# EasyBMS.net
KiCad netlist of a schematic drawn in EAGLE
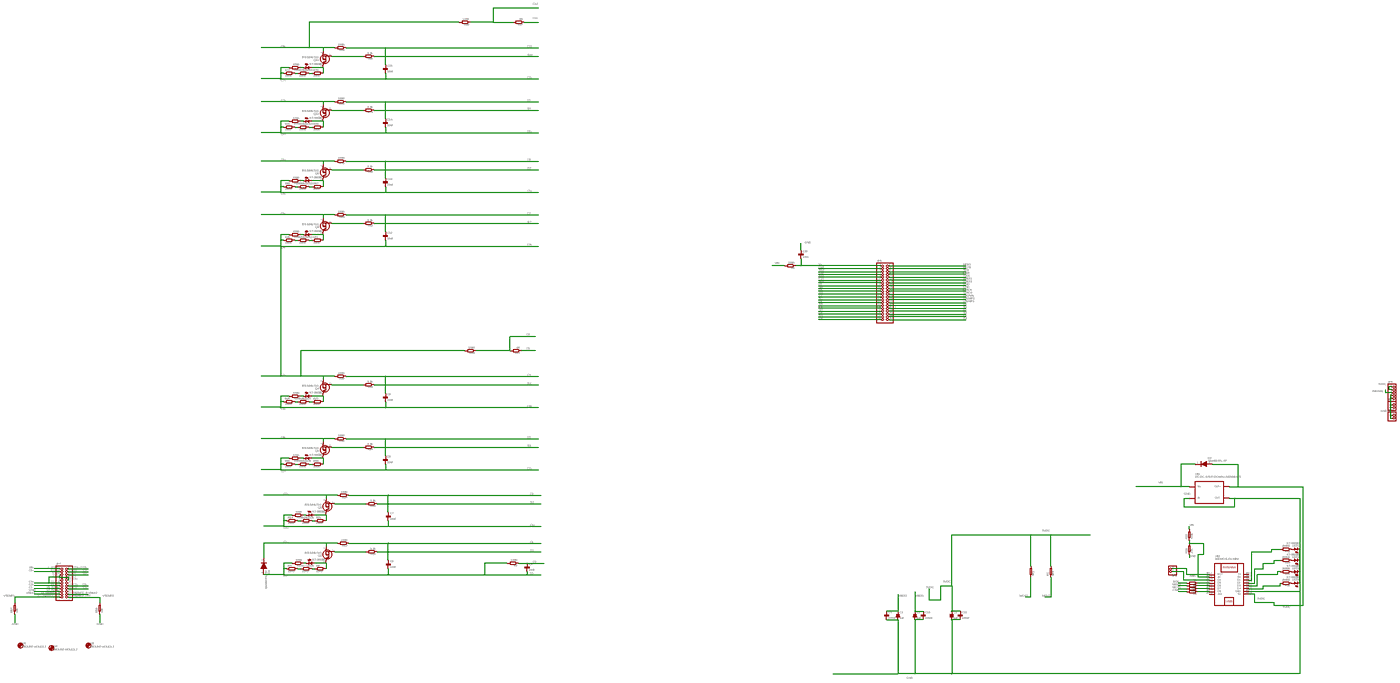
[diagram p0: schematic, sheet 1, overview]
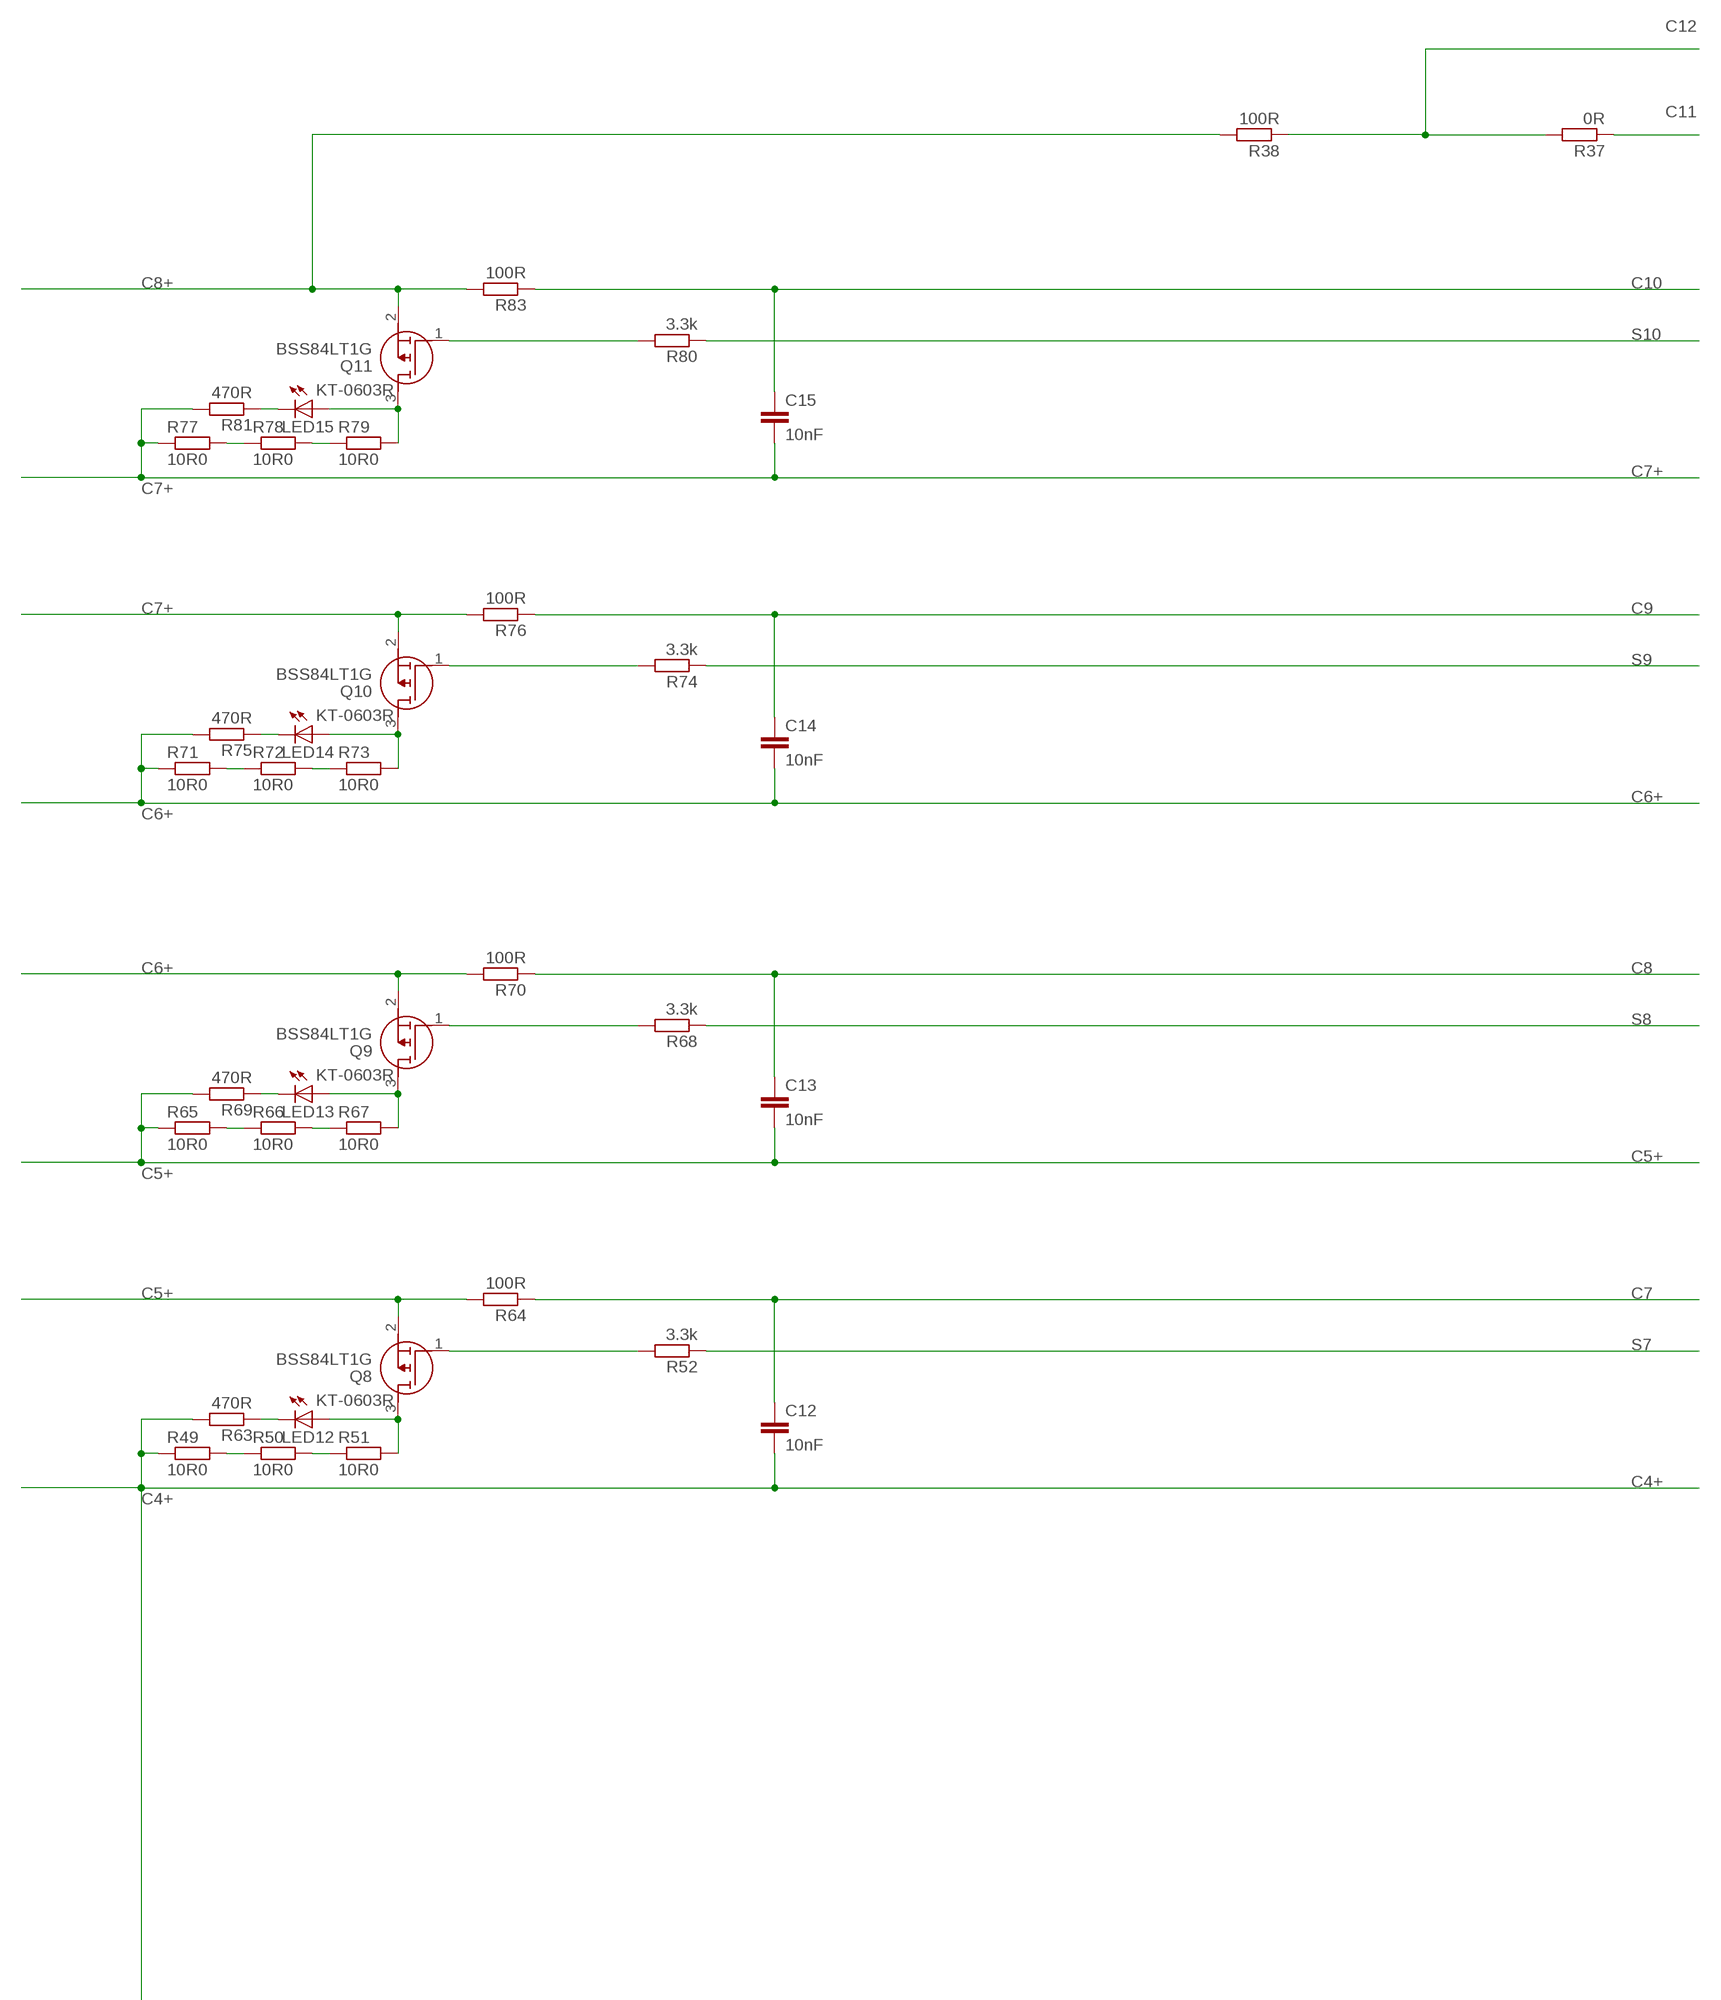
[diagram p1: schematic, sheet 1, part 1 of 4]
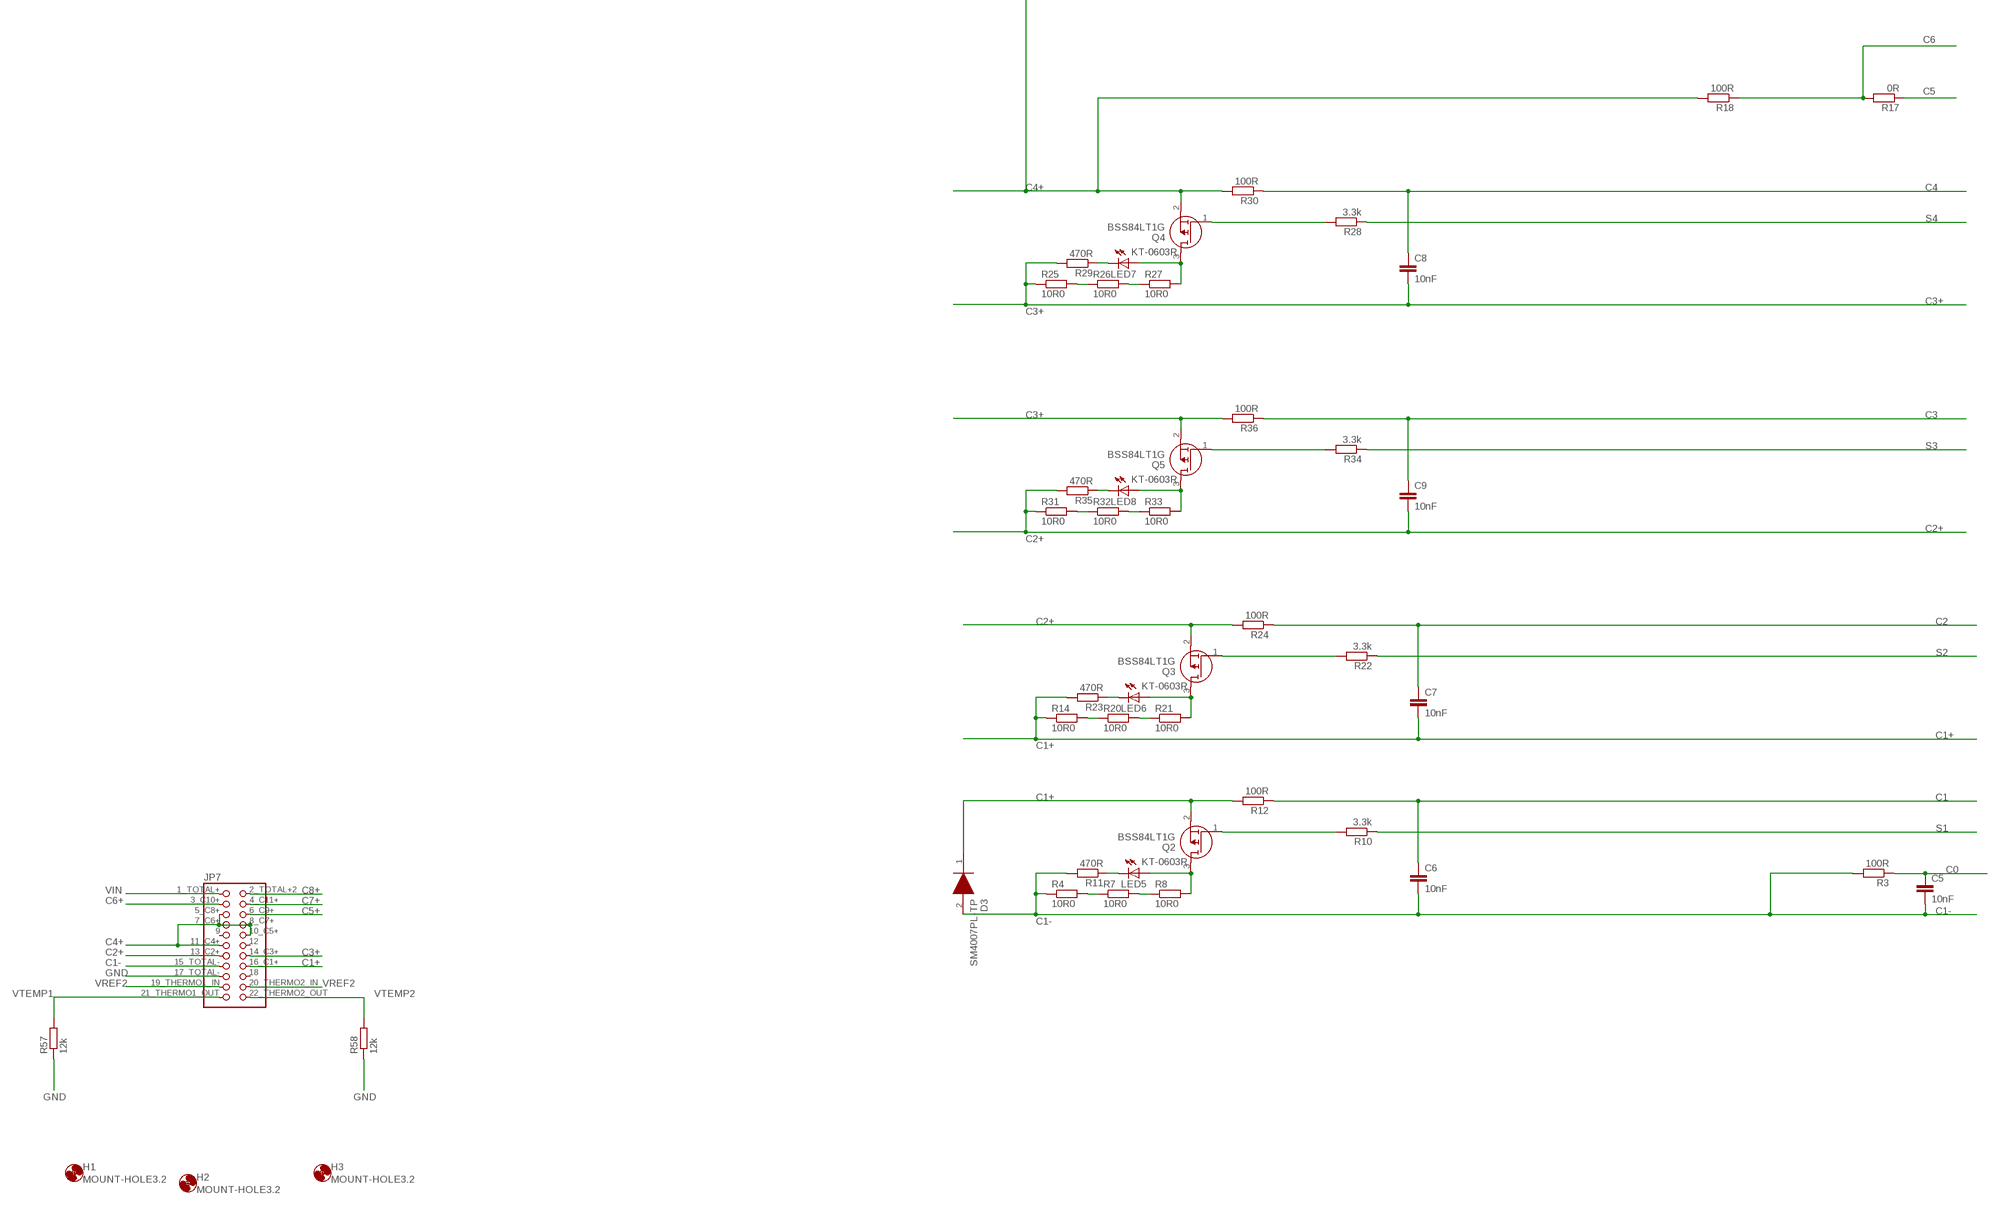
[diagram p2: schematic, sheet 1, part 2 of 4]
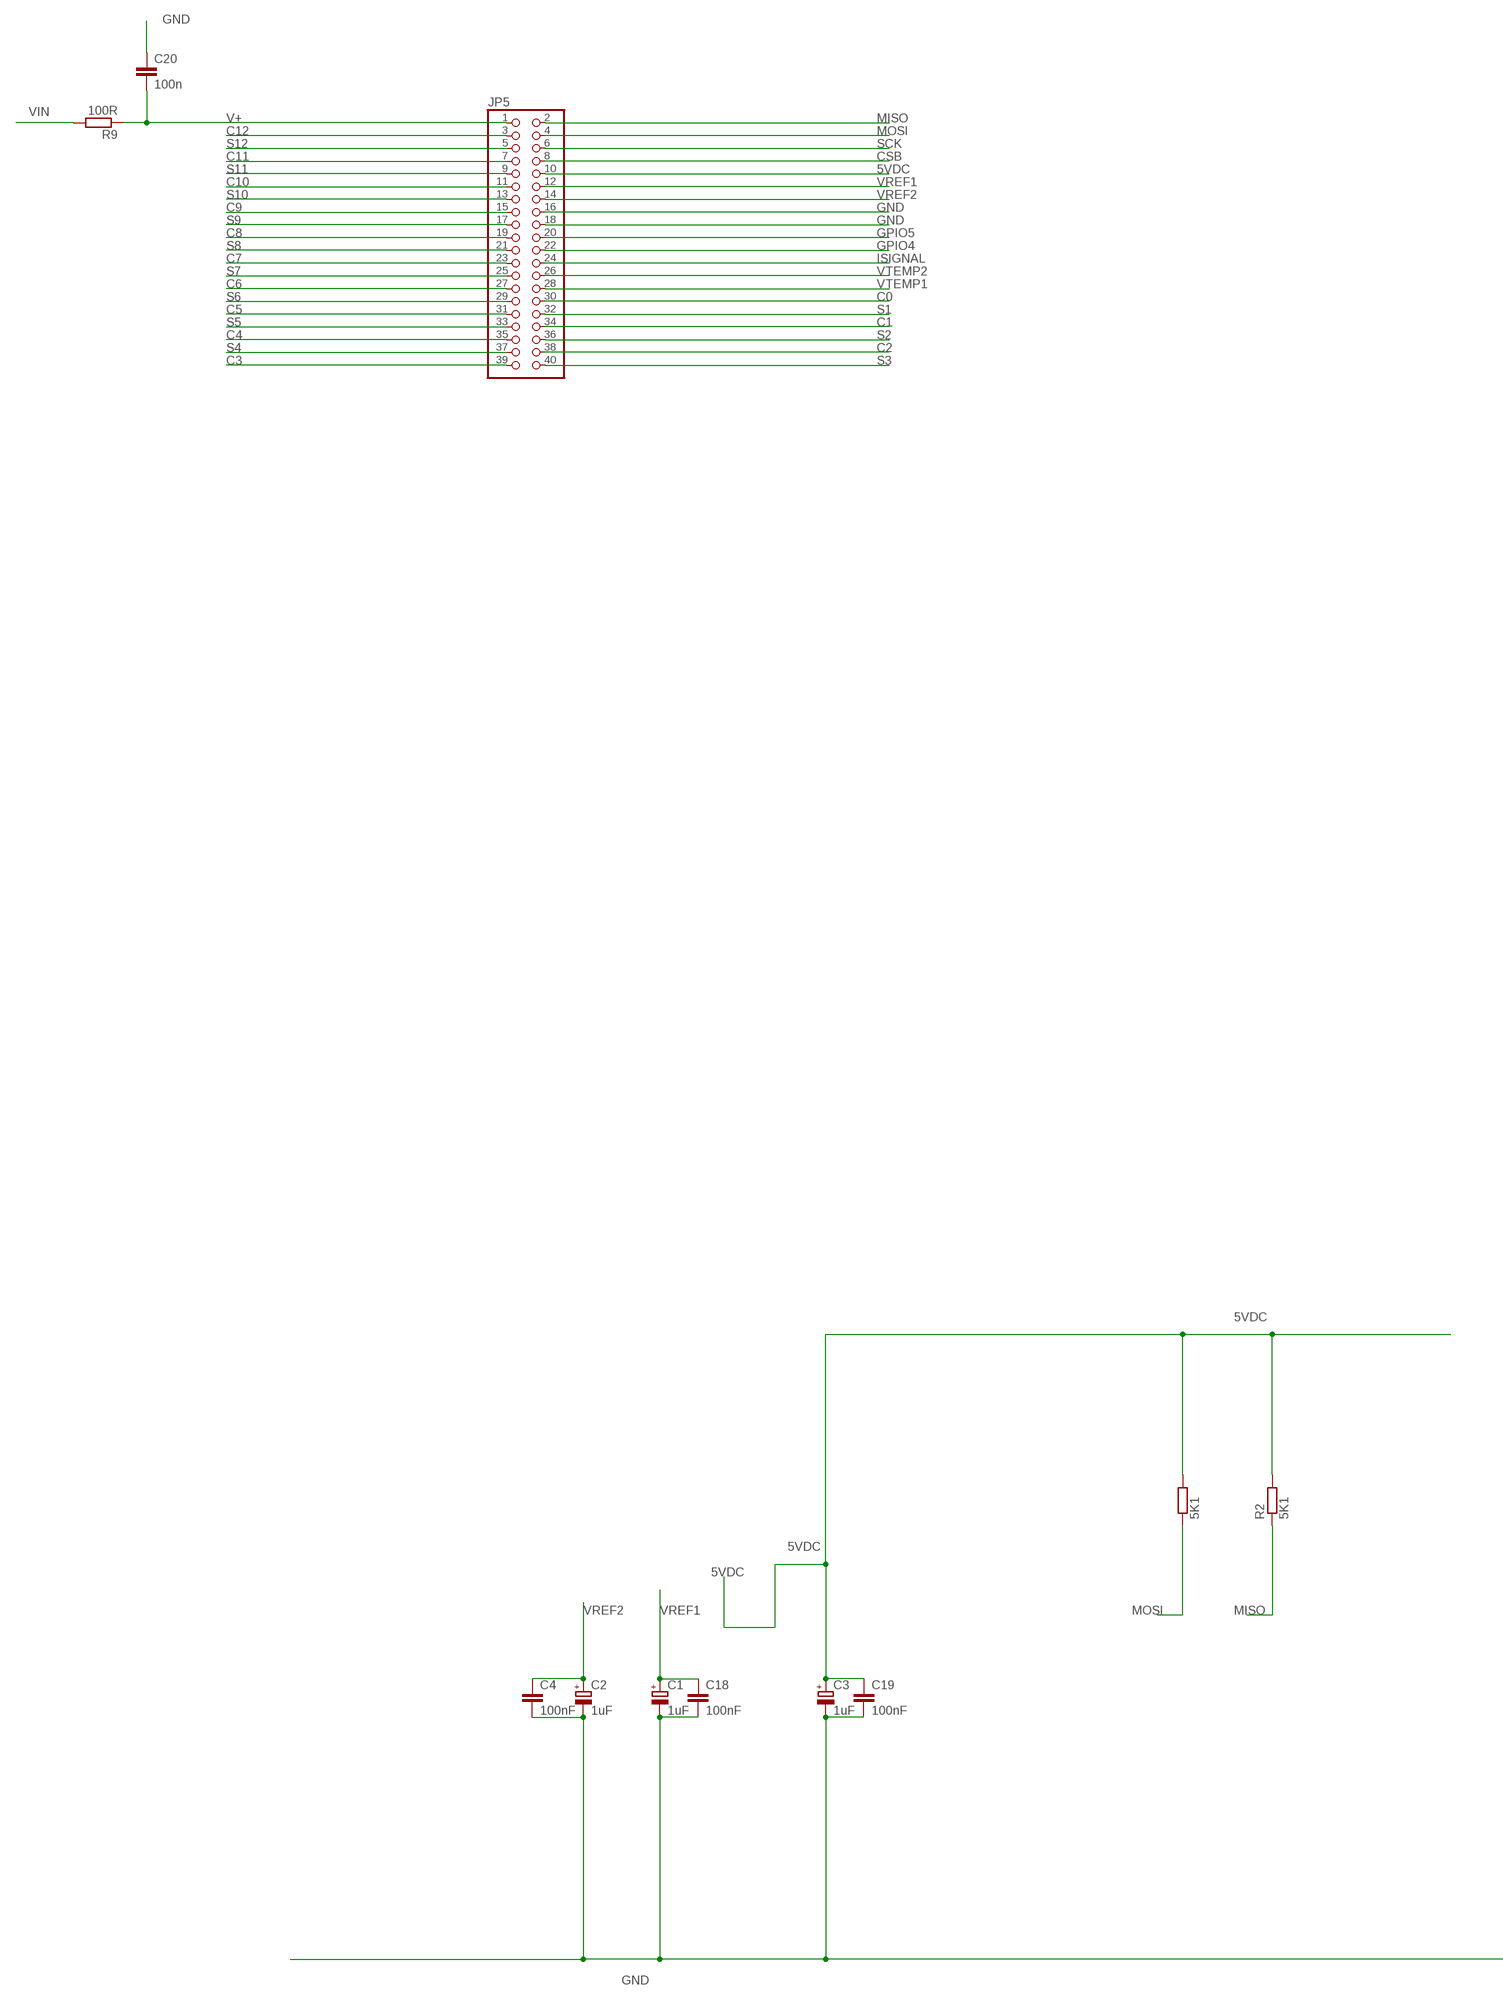
[diagram p3: schematic, sheet 1, part 3 of 4]
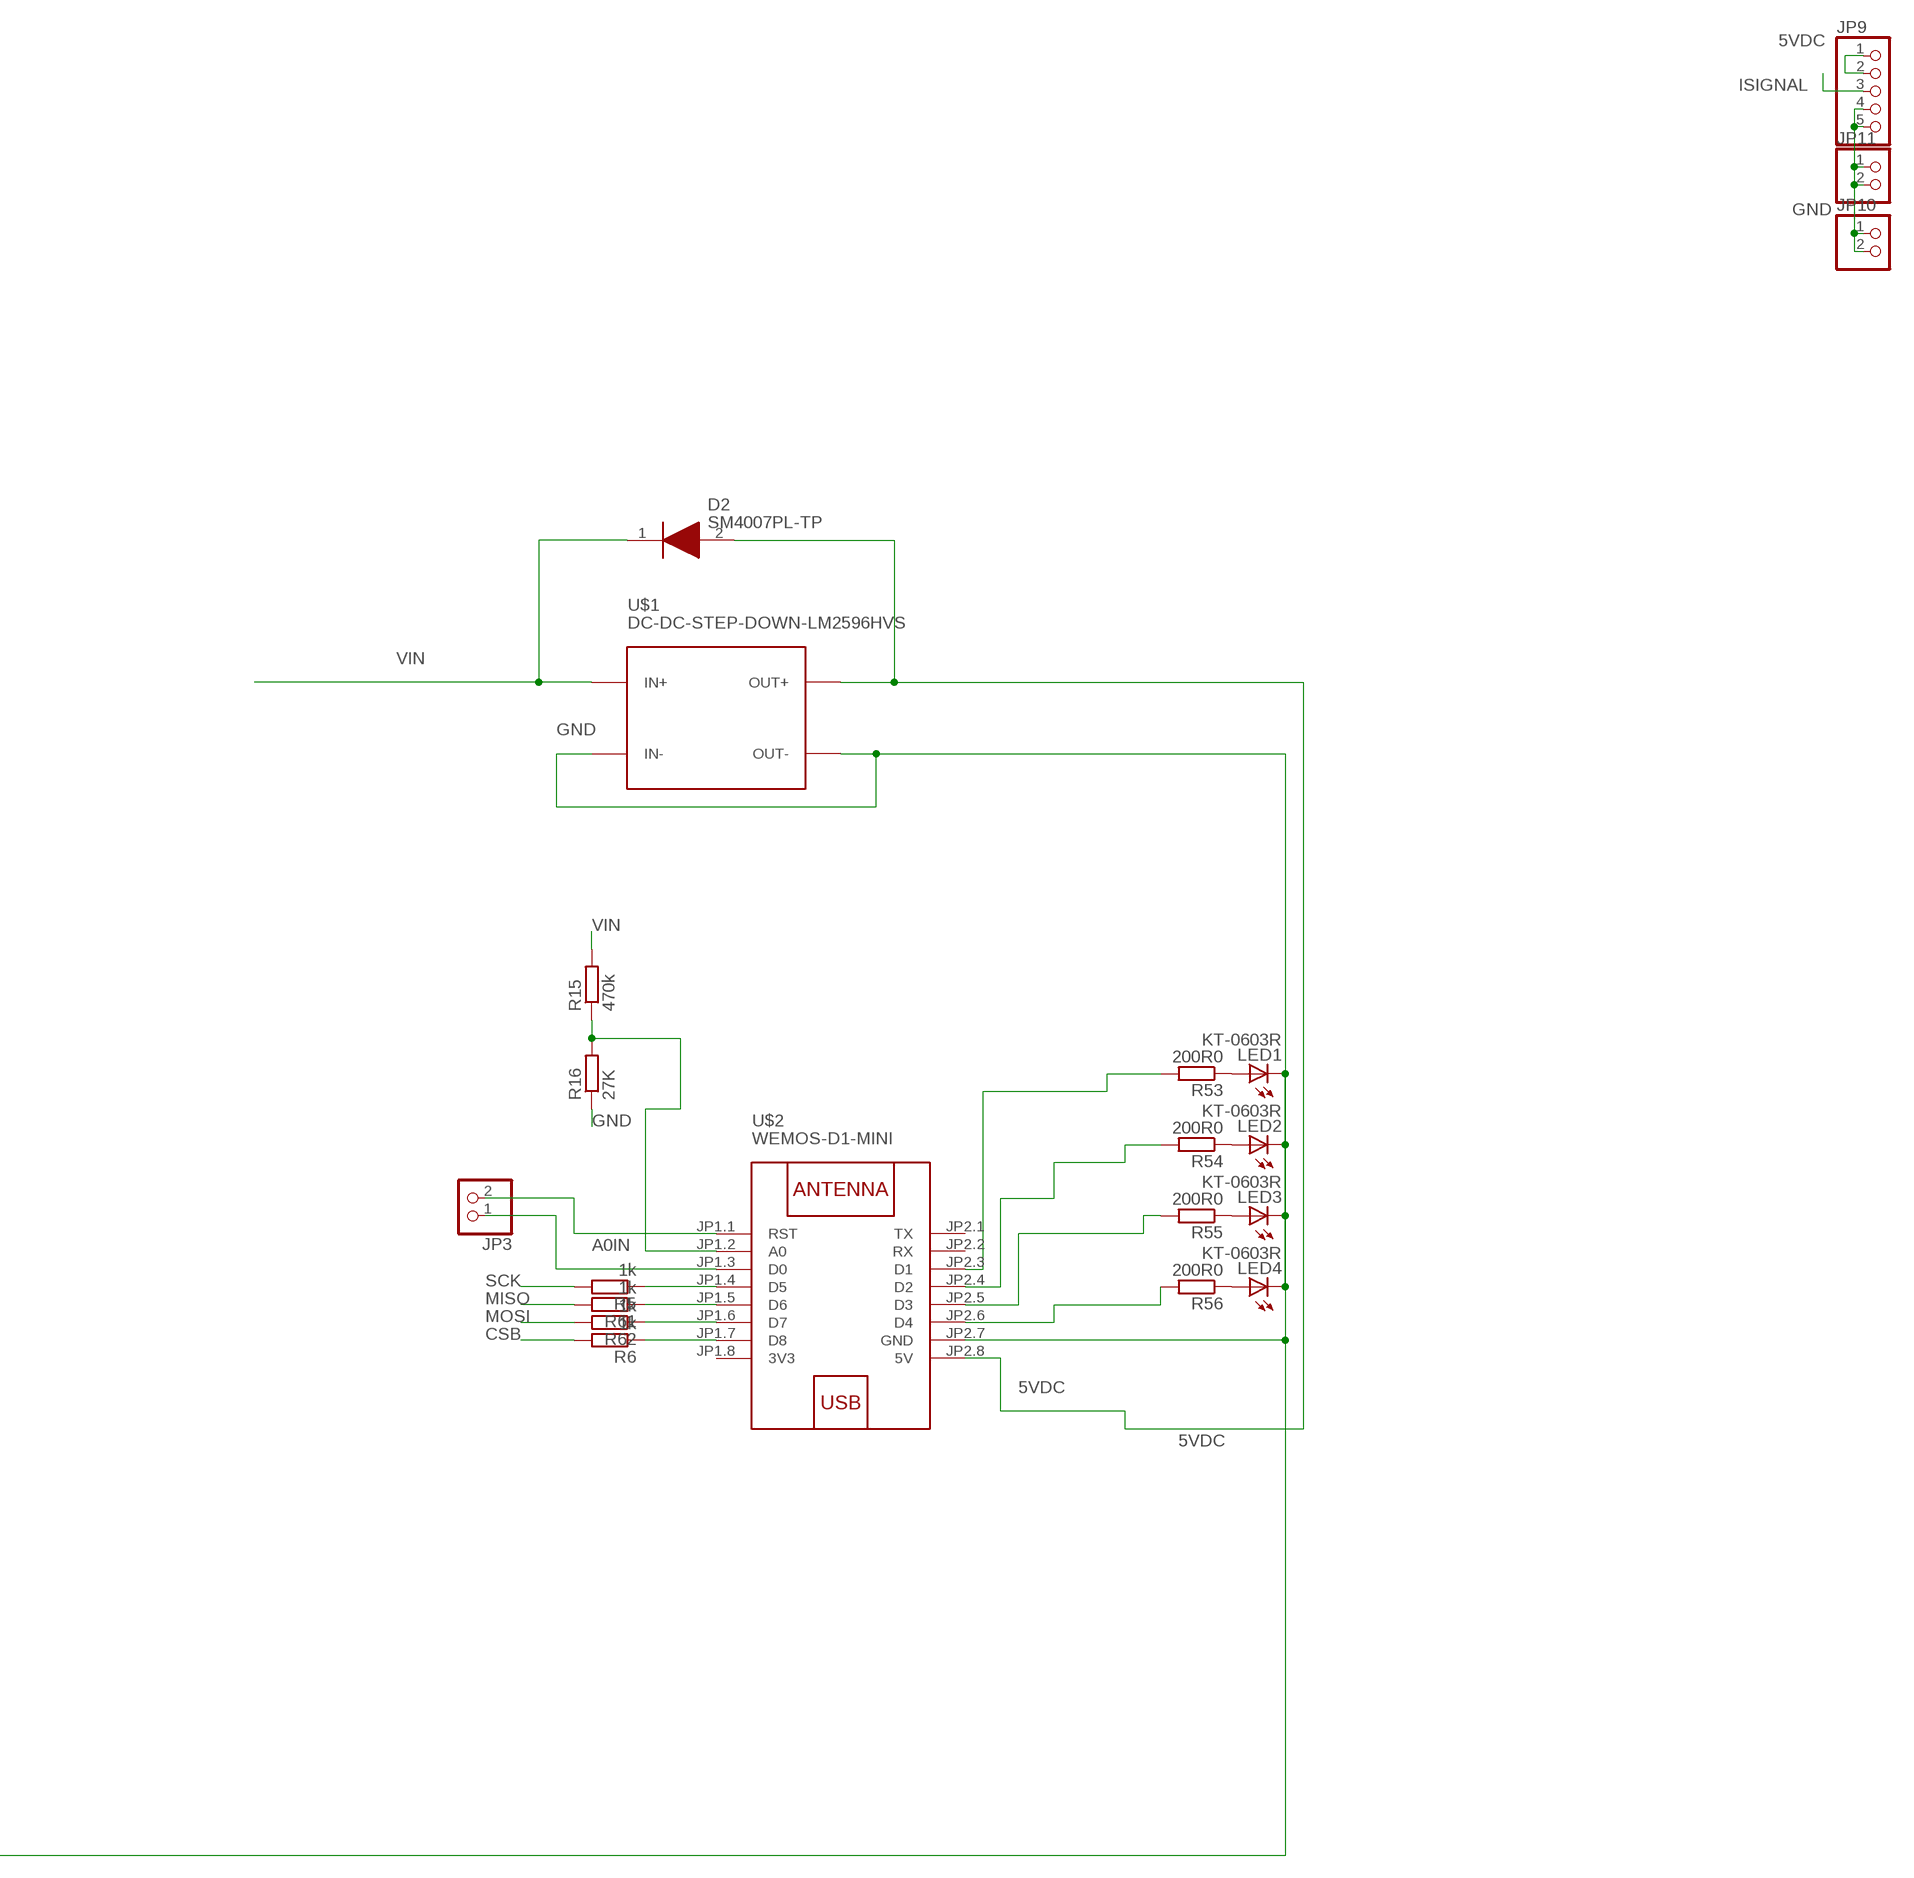
[diagram p4: schematic, sheet 1, part 4 of 4]

(export (version "E")
  (design (tool "Eeschema 10.0.6"))
  (components
    (comp (ref "C1")
      (value "1uF")
      (footprint "eagle-import:E2,5-6")
      (libsource (lib "eagle-import") (part "CPOL-EUE2.5-6"))
    )
    (comp (ref "C2")
      (value "1uF")
      (footprint "eagle-import:E2,5-6")
      (libsource (lib "eagle-import") (part "CPOL-EUE2.5-6"))
    )
    (comp (ref "C3")
      (value "1uF")
      (footprint "eagle-import:E2,5-6")
      (libsource (lib "eagle-import") (part "CPOL-EUE2.5-6"))
    )
    (comp (ref "C4")
      (value "100nF")
      (footprint "eagle-import:C1206")
      (libsource (lib "eagle-import") (part "C-EUC1206"))
    )
    (comp (ref "C5")
      (value "10nF")
      (footprint "eagle-import:C0402")
      (libsource (lib "eagle-import") (part "C-EUC0402"))
    )
    (comp (ref "C6")
      (value "10nF")
      (footprint "eagle-import:C0402")
      (libsource (lib "eagle-import") (part "C-EUC0402"))
    )
    (comp (ref "C7")
      (value "10nF")
      (footprint "eagle-import:C0402")
      (libsource (lib "eagle-import") (part "C-EUC0402"))
    )
    (comp (ref "C8")
      (value "10nF")
      (footprint "eagle-import:C0402")
      (libsource (lib "eagle-import") (part "C-EUC0402"))
    )
    (comp (ref "C9")
      (value "10nF")
      (footprint "eagle-import:C0402")
      (libsource (lib "eagle-import") (part "C-EUC0402"))
    )
    (comp (ref "C12")
      (value "10nF")
      (footprint "eagle-import:C0402")
      (libsource (lib "eagle-import") (part "C-EUC0402"))
    )
    (comp (ref "C13")
      (value "10nF")
      (footprint "eagle-import:C0402")
      (libsource (lib "eagle-import") (part "C-EUC0402"))
    )
    (comp (ref "C14")
      (value "10nF")
      (footprint "eagle-import:C0402")
      (libsource (lib "eagle-import") (part "C-EUC0402"))
    )
    (comp (ref "C15")
      (value "10nF")
      (footprint "eagle-import:C0402")
      (libsource (lib "eagle-import") (part "C-EUC0402"))
    )
    (comp (ref "C18")
      (value "100nF")
      (footprint "eagle-import:C1206")
      (libsource (lib "eagle-import") (part "C-EUC1206"))
    )
    (comp (ref "C19")
      (value "100nF")
      (footprint "eagle-import:C1206")
      (libsource (lib "eagle-import") (part "C-EUC1206"))
    )
    (comp (ref "C20")
      (value "100n")
      (footprint "eagle-import:C0402")
      (libsource (lib "eagle-import") (part "C-EUC0402"))
    )
    (comp (ref "D2")
      (value "SM4007PL-TP")
      (footprint "eagle-import:SODFL3616X135N")
      (fields (field (name "MOUSER_PART_NUMBER") "833-SM4007PL-TP"))
      (libsource (lib "eagle-import") (part "SM4007PL-TP"))
    )
    (comp (ref "D3")
      (value "SM4007PL-TP")
      (footprint "eagle-import:SODFL3616X135N")
      (fields (field (name "MOUSER_PART_NUMBER") "833-SM4007PL-TP"))
      (libsource (lib "eagle-import") (part "SM4007PL-TP"))
    )
    (comp (ref "H1")
      (value "MOUNT-HOLE3.2")
      (footprint "eagle-import:3,2")
      (libsource (lib "eagle-import") (part "MOUNT-HOLE3.2"))
    )
    (comp (ref "H2")
      (value "MOUNT-HOLE3.2")
      (footprint "eagle-import:3,2")
      (libsource (lib "eagle-import") (part "MOUNT-HOLE3.2"))
    )
    (comp (ref "H3")
      (value "MOUNT-HOLE3.2")
      (footprint "eagle-import:3,2")
      (libsource (lib "eagle-import") (part "MOUNT-HOLE3.2"))
    )
    (comp (ref "JP3")
      (value "PINHD-1X2")
      (footprint "eagle-import:1X02")
      (libsource (lib "eagle-import") (part "pinhead_own_PINHD-1X2"))
    )
    (comp (ref "JP5")
      (value "PINHD-2X20")
      (footprint "eagle-import:2X20")
      (libsource (lib "eagle-import") (part "PINHD-2X20"))
    )
    (comp (ref "JP7")
      (value "PINHD-2X11_MEB12S")
      (footprint "eagle-import:2X11_MEB12S")
      (libsource (lib "eagle-import") (part "PINHD-2X11_MEB12S"))
    )
    (comp (ref "JP9")
      (value "PINHD-1X5")
      (footprint "eagle-import:1X05")
      (libsource (lib "eagle-import") (part "PINHD-1X5"))
    )
    (comp (ref "JP10")
      (value "PINHD-1X2")
      (footprint "eagle-import:1X02")
      (libsource (lib "eagle-import") (part "PINHD-1X2"))
    )
    (comp (ref "JP11")
      (value "PINHD-1X2")
      (footprint "eagle-import:1X02")
      (libsource (lib "eagle-import") (part "PINHD-1X2"))
    )
    (comp (ref "LED1")
      (value "KT-0603R")
      (footprint "eagle-import:CHIPLED_0603")
      (libsource (lib "eagle-import") (part "LEDCHIPLED_0603"))
    )
    (comp (ref "LED2")
      (value "KT-0603R")
      (footprint "eagle-import:CHIPLED_0603")
      (libsource (lib "eagle-import") (part "LEDCHIPLED_0603"))
    )
    (comp (ref "LED3")
      (value "KT-0603R")
      (footprint "eagle-import:CHIPLED_0603")
      (libsource (lib "eagle-import") (part "LEDCHIPLED_0603"))
    )
    (comp (ref "LED4")
      (value "KT-0603R")
      (footprint "eagle-import:CHIPLED_0603")
      (libsource (lib "eagle-import") (part "LEDCHIPLED_0603"))
    )
    (comp (ref "LED5")
      (value "KT-0603R")
      (footprint "eagle-import:CHIPLED_0603")
      (libsource (lib "eagle-import") (part "LEDCHIPLED_0603"))
    )
    (comp (ref "LED6")
      (value "KT-0603R")
      (footprint "eagle-import:CHIPLED_0603")
      (libsource (lib "eagle-import") (part "LEDCHIPLED_0603"))
    )
    (comp (ref "LED7")
      (value "KT-0603R")
      (footprint "eagle-import:CHIPLED_0603")
      (libsource (lib "eagle-import") (part "LEDCHIPLED_0603"))
    )
    (comp (ref "LED8")
      (value "KT-0603R")
      (footprint "eagle-import:CHIPLED_0603")
      (libsource (lib "eagle-import") (part "LEDCHIPLED_0603"))
    )
    (comp (ref "LED12")
      (value "KT-0603R")
      (footprint "eagle-import:CHIPLED_0603")
      (libsource (lib "eagle-import") (part "LEDCHIPLED_0603"))
    )
    (comp (ref "LED13")
      (value "KT-0603R")
      (footprint "eagle-import:CHIPLED_0603")
      (libsource (lib "eagle-import") (part "LEDCHIPLED_0603"))
    )
    (comp (ref "LED14")
      (value "KT-0603R")
      (footprint "eagle-import:CHIPLED_0603")
      (libsource (lib "eagle-import") (part "LEDCHIPLED_0603"))
    )
    (comp (ref "LED15")
      (value "KT-0603R")
      (footprint "eagle-import:CHIPLED_0603")
      (libsource (lib "eagle-import") (part "LEDCHIPLED_0603"))
    )
    (comp (ref "Q2")
      (value "BSS84LT1G")
      (footprint "eagle-import:SOT96P237X111-3N")
      (fields (field (name "MOUSER_PART_NUMBER") "863-BSS84LT1G"))
      (libsource (lib "eagle-import") (part "BSS84LT1G"))
    )
    (comp (ref "Q3")
      (value "BSS84LT1G")
      (footprint "eagle-import:SOT96P237X111-3N")
      (fields (field (name "MOUSER_PART_NUMBER") "863-BSS84LT1G"))
      (libsource (lib "eagle-import") (part "BSS84LT1G"))
    )
    (comp (ref "Q4")
      (value "BSS84LT1G")
      (footprint "eagle-import:SOT96P237X111-3N")
      (fields (field (name "MOUSER_PART_NUMBER") "863-BSS84LT1G"))
      (libsource (lib "eagle-import") (part "BSS84LT1G"))
    )
    (comp (ref "Q5")
      (value "BSS84LT1G")
      (footprint "eagle-import:SOT96P237X111-3N")
      (fields (field (name "MOUSER_PART_NUMBER") "863-BSS84LT1G"))
      (libsource (lib "eagle-import") (part "BSS84LT1G"))
    )
    (comp (ref "Q8")
      (value "BSS84LT1G")
      (footprint "eagle-import:SOT96P237X111-3N")
      (fields (field (name "MOUSER_PART_NUMBER") "863-BSS84LT1G"))
      (libsource (lib "eagle-import") (part "BSS84LT1G"))
    )
    (comp (ref "Q9")
      (value "BSS84LT1G")
      (footprint "eagle-import:SOT96P237X111-3N")
      (fields (field (name "MOUSER_PART_NUMBER") "863-BSS84LT1G"))
      (libsource (lib "eagle-import") (part "BSS84LT1G"))
    )
    (comp (ref "Q10")
      (value "BSS84LT1G")
      (footprint "eagle-import:SOT96P237X111-3N")
      (fields (field (name "MOUSER_PART_NUMBER") "863-BSS84LT1G"))
      (libsource (lib "eagle-import") (part "BSS84LT1G"))
    )
    (comp (ref "Q11")
      (value "BSS84LT1G")
      (footprint "eagle-import:SOT96P237X111-3N")
      (fields (field (name "MOUSER_PART_NUMBER") "863-BSS84LT1G"))
      (libsource (lib "eagle-import") (part "BSS84LT1G"))
    )
    (comp (ref "R1")
      (value "5K1")
      (footprint "eagle-import:R0603")
      (libsource (lib "eagle-import") (part "R-EU_R0603"))
    )
    (comp (ref "R2")
      (value "5K1")
      (footprint "eagle-import:R0603")
      (libsource (lib "eagle-import") (part "R-EU_R0603"))
    )
    (comp (ref "R3")
      (value "100R")
      (footprint "eagle-import:R0402")
      (libsource (lib "eagle-import") (part "R-EU_R0402"))
    )
    (comp (ref "R4")
      (value "10R0")
      (footprint "eagle-import:R1206")
      (libsource (lib "eagle-import") (part "R-EU_R1206"))
    )
    (comp (ref "R5")
      (value "1k")
      (footprint "eagle-import:R0603")
      (libsource (lib "eagle-import") (part "R-EU_R0603"))
    )
    (comp (ref "R6")
      (value "1k")
      (footprint "eagle-import:R0603")
      (libsource (lib "eagle-import") (part "R-EU_R0603"))
    )
    (comp (ref "R7")
      (value "10R0")
      (footprint "eagle-import:R1206")
      (libsource (lib "eagle-import") (part "R-EU_R1206"))
    )
    (comp (ref "R8")
      (value "10R0")
      (footprint "eagle-import:R1206")
      (libsource (lib "eagle-import") (part "R-EU_R1206"))
    )
    (comp (ref "R9")
      (value "100R")
      (footprint "eagle-import:R0402")
      (libsource (lib "eagle-import") (part "R-EU_R0402"))
    )
    (comp (ref "R10")
      (value "3.3k")
      (footprint "eagle-import:R0402")
      (libsource (lib "eagle-import") (part "R-EU_R0402"))
    )
    (comp (ref "R11")
      (value "470R")
      (footprint "eagle-import:R0402")
      (libsource (lib "eagle-import") (part "R-EU_R0402"))
    )
    (comp (ref "R12")
      (value "100R")
      (footprint "eagle-import:R0402")
      (libsource (lib "eagle-import") (part "R-EU_R0402"))
    )
    (comp (ref "R14")
      (value "10R0")
      (footprint "eagle-import:R1206")
      (libsource (lib "eagle-import") (part "R-EU_R1206"))
    )
    (comp (ref "R15")
      (value "470k")
      (footprint "eagle-import:R0603")
      (libsource (lib "eagle-import") (part "R-EU_R0603"))
    )
    (comp (ref "R16")
      (value "27K")
      (footprint "eagle-import:R0603")
      (libsource (lib "eagle-import") (part "R-EU_R0603"))
    )
    (comp (ref "R17")
      (value "0R")
      (footprint "eagle-import:R0402")
      (libsource (lib "eagle-import") (part "R-EU_R0402"))
    )
    (comp (ref "R18")
      (value "100R")
      (footprint "eagle-import:R0402")
      (libsource (lib "eagle-import") (part "R-EU_R0402"))
    )
    (comp (ref "R20")
      (value "10R0")
      (footprint "eagle-import:R1206")
      (libsource (lib "eagle-import") (part "R-EU_R1206"))
    )
    (comp (ref "R21")
      (value "10R0")
      (footprint "eagle-import:R1206")
      (libsource (lib "eagle-import") (part "R-EU_R1206"))
    )
    (comp (ref "R22")
      (value "3.3k")
      (footprint "eagle-import:R0402")
      (libsource (lib "eagle-import") (part "R-EU_R0402"))
    )
    (comp (ref "R23")
      (value "470R")
      (footprint "eagle-import:R0402")
      (libsource (lib "eagle-import") (part "R-EU_R0402"))
    )
    (comp (ref "R24")
      (value "100R")
      (footprint "eagle-import:R0402")
      (libsource (lib "eagle-import") (part "R-EU_R0402"))
    )
    (comp (ref "R25")
      (value "10R0")
      (footprint "eagle-import:R1206")
      (libsource (lib "eagle-import") (part "R-EU_R1206"))
    )
    (comp (ref "R26")
      (value "10R0")
      (footprint "eagle-import:R1206")
      (libsource (lib "eagle-import") (part "R-EU_R1206"))
    )
    (comp (ref "R27")
      (value "10R0")
      (footprint "eagle-import:R1206")
      (libsource (lib "eagle-import") (part "R-EU_R1206"))
    )
    (comp (ref "R28")
      (value "3.3k")
      (footprint "eagle-import:R0402")
      (libsource (lib "eagle-import") (part "R-EU_R0402"))
    )
    (comp (ref "R29")
      (value "470R")
      (footprint "eagle-import:R0402")
      (libsource (lib "eagle-import") (part "R-EU_R0402"))
    )
    (comp (ref "R30")
      (value "100R")
      (footprint "eagle-import:R0402")
      (libsource (lib "eagle-import") (part "R-EU_R0402"))
    )
    (comp (ref "R31")
      (value "10R0")
      (footprint "eagle-import:R1206")
      (libsource (lib "eagle-import") (part "R-EU_R1206"))
    )
    (comp (ref "R32")
      (value "10R0")
      (footprint "eagle-import:R1206")
      (libsource (lib "eagle-import") (part "R-EU_R1206"))
    )
    (comp (ref "R33")
      (value "10R0")
      (footprint "eagle-import:R1206")
      (libsource (lib "eagle-import") (part "R-EU_R1206"))
    )
    (comp (ref "R34")
      (value "3.3k")
      (footprint "eagle-import:R0402")
      (libsource (lib "eagle-import") (part "R-EU_R0402"))
    )
    (comp (ref "R35")
      (value "470R")
      (footprint "eagle-import:R0402")
      (libsource (lib "eagle-import") (part "R-EU_R0402"))
    )
    (comp (ref "R36")
      (value "100R")
      (footprint "eagle-import:R0402")
      (libsource (lib "eagle-import") (part "R-EU_R0402"))
    )
    (comp (ref "R37")
      (value "0R")
      (footprint "eagle-import:R0402")
      (libsource (lib "eagle-import") (part "R-EU_R0402"))
    )
    (comp (ref "R38")
      (value "100R")
      (footprint "eagle-import:R0402")
      (libsource (lib "eagle-import") (part "R-EU_R0402"))
    )
    (comp (ref "R49")
      (value "10R0")
      (footprint "eagle-import:R1206")
      (libsource (lib "eagle-import") (part "R-EU_R1206"))
    )
    (comp (ref "R50")
      (value "10R0")
      (footprint "eagle-import:R1206")
      (libsource (lib "eagle-import") (part "R-EU_R1206"))
    )
    (comp (ref "R51")
      (value "10R0")
      (footprint "eagle-import:R1206")
      (libsource (lib "eagle-import") (part "R-EU_R1206"))
    )
    (comp (ref "R52")
      (value "3.3k")
      (footprint "eagle-import:R0402")
      (libsource (lib "eagle-import") (part "R-EU_R0402"))
    )
    (comp (ref "R53")
      (value "200R0")
      (footprint "eagle-import:R0603")
      (libsource (lib "eagle-import") (part "R-EU_R0603"))
    )
    (comp (ref "R54")
      (value "200R0")
      (footprint "eagle-import:R0603")
      (libsource (lib "eagle-import") (part "R-EU_R0603"))
    )
    (comp (ref "R55")
      (value "200R0")
      (footprint "eagle-import:R0603")
      (libsource (lib "eagle-import") (part "R-EU_R0603"))
    )
    (comp (ref "R56")
      (value "200R0")
      (footprint "eagle-import:R0603")
      (libsource (lib "eagle-import") (part "R-EU_R0603"))
    )
    (comp (ref "R57")
      (value "12k")
      (footprint "eagle-import:R0603")
      (libsource (lib "eagle-import") (part "R-EU_R0603"))
    )
    (comp (ref "R58")
      (value "12k")
      (footprint "eagle-import:R0603")
      (libsource (lib "eagle-import") (part "R-EU_R0603"))
    )
    (comp (ref "R61")
      (value "1k")
      (footprint "eagle-import:R0603")
      (libsource (lib "eagle-import") (part "R-EU_R0603"))
    )
    (comp (ref "R62")
      (value "1k")
      (footprint "eagle-import:R0603")
      (libsource (lib "eagle-import") (part "R-EU_R0603"))
    )
    (comp (ref "R63")
      (value "470R")
      (footprint "eagle-import:R0402")
      (libsource (lib "eagle-import") (part "R-EU_R0402"))
    )
    (comp (ref "R64")
      (value "100R")
      (footprint "eagle-import:R0402")
      (libsource (lib "eagle-import") (part "R-EU_R0402"))
    )
    (comp (ref "R65")
      (value "10R0")
      (footprint "eagle-import:R1206")
      (libsource (lib "eagle-import") (part "R-EU_R1206"))
    )
    (comp (ref "R66")
      (value "10R0")
      (footprint "eagle-import:R1206")
      (libsource (lib "eagle-import") (part "R-EU_R1206"))
    )
    (comp (ref "R67")
      (value "10R0")
      (footprint "eagle-import:R1206")
      (libsource (lib "eagle-import") (part "R-EU_R1206"))
    )
    (comp (ref "R68")
      (value "3.3k")
      (footprint "eagle-import:R0402")
      (libsource (lib "eagle-import") (part "R-EU_R0402"))
    )
    (comp (ref "R69")
      (value "470R")
      (footprint "eagle-import:R0402")
      (libsource (lib "eagle-import") (part "R-EU_R0402"))
    )
    (comp (ref "R70")
      (value "100R")
      (footprint "eagle-import:R0402")
      (libsource (lib "eagle-import") (part "R-EU_R0402"))
    )
    (comp (ref "R71")
      (value "10R0")
      (footprint "eagle-import:R1206")
      (libsource (lib "eagle-import") (part "R-EU_R1206"))
    )
    (comp (ref "R72")
      (value "10R0")
      (footprint "eagle-import:R1206")
      (libsource (lib "eagle-import") (part "R-EU_R1206"))
    )
    (comp (ref "R73")
      (value "10R0")
      (footprint "eagle-import:R1206")
      (libsource (lib "eagle-import") (part "R-EU_R1206"))
    )
    (comp (ref "R74")
      (value "3.3k")
      (footprint "eagle-import:R0402")
      (libsource (lib "eagle-import") (part "R-EU_R0402"))
    )
    (comp (ref "R75")
      (value "470R")
      (footprint "eagle-import:R0402")
      (libsource (lib "eagle-import") (part "R-EU_R0402"))
    )
    (comp (ref "R76")
      (value "100R")
      (footprint "eagle-import:R0402")
      (libsource (lib "eagle-import") (part "R-EU_R0402"))
    )
    (comp (ref "R77")
      (value "10R0")
      (footprint "eagle-import:R1206")
      (libsource (lib "eagle-import") (part "R-EU_R1206"))
    )
    (comp (ref "R78")
      (value "10R0")
      (footprint "eagle-import:R1206")
      (libsource (lib "eagle-import") (part "R-EU_R1206"))
    )
    (comp (ref "R79")
      (value "10R0")
      (footprint "eagle-import:R1206")
      (libsource (lib "eagle-import") (part "R-EU_R1206"))
    )
    (comp (ref "R80")
      (value "3.3k")
      (footprint "eagle-import:R0402")
      (libsource (lib "eagle-import") (part "R-EU_R0402"))
    )
    (comp (ref "R81")
      (value "470R")
      (footprint "eagle-import:R0402")
      (libsource (lib "eagle-import") (part "R-EU_R0402"))
    )
    (comp (ref "R83")
      (value "100R")
      (footprint "eagle-import:R0402")
      (libsource (lib "eagle-import") (part "R-EU_R0402"))
    )
    (comp (ref "U$1")
      (value "DC-DC-STEP-DOWN-LM2596HVS")
      (footprint "eagle-import:DC-DC-STEP-DOWN-LM2596HVS")
      (libsource (lib "eagle-import") (part "DC-DC-STEP-DOWN-LM2596HVS"))
    )
    (comp (ref "U$2")
      (value "WEMOS-D1-MINI")
      (footprint "eagle-import:WEMOS-D1-MINI")
      (libsource (lib "eagle-import") (part "WEMOS-D1-MINI"))
    )
  )
  (nets
    (net (code "1") (name "/3V3") (class "Default")
      (node (ref "U$2") (pin "JP1.8") (pinfunction "3V3_JP1.8") (pintype "power_in"))
    )
    (net (code "2") (name "/5VDC") (class "Default")
      (node (ref "C19") (pin "1") (pinfunction "1_1") (pintype "passive"))
      (node (ref "C3") (pin "+") (pinfunction "+_+") (pintype "passive"))
      (node (ref "D2") (pin "2") (pinfunction "A_2") (pintype "bidirectional"))
      (node (ref "JP5") (pin "10") (pinfunction "10_10") (pintype "passive"))
      (node (ref "JP9") (pin "1") (pinfunction "1_1") (pintype "passive"))
      (node (ref "JP9") (pin "2") (pinfunction "2_2") (pintype "passive"))
      (node (ref "R1") (pin "2") (pinfunction "2_2") (pintype "passive"))
      (node (ref "R2") (pin "2") (pinfunction "2_2") (pintype "passive"))
      (node (ref "U$1") (pin "OUT+") (pinfunction "OUT+_OUT+") (pintype "bidirectional"))
      (node (ref "U$2") (pin "JP2.8") (pinfunction "5V_JP2.8") (pintype "power_in"))
    )
    (net (code "3") (name "/A0IN") (class "Default")
      (node (ref "R15") (pin "1") (pinfunction "1_1") (pintype "passive"))
      (node (ref "R16") (pin "2") (pinfunction "2_2") (pintype "passive"))
      (node (ref "U$2") (pin "JP1.2") (pinfunction "A0_JP1.2") (pintype "bidirectional"))
    )
    (net (code "4") (name "/C0") (class "Default")
      (node (ref "C5") (pin "1") (pinfunction "1_1") (pintype "passive"))
      (node (ref "JP5") (pin "30") (pinfunction "30_30") (pintype "passive"))
      (node (ref "R3") (pin "1") (pinfunction "1_1") (pintype "passive"))
    )
    (net (code "5") (name "/C1") (class "Default")
      (node (ref "C6") (pin "1") (pinfunction "1_1") (pintype "passive"))
      (node (ref "JP5") (pin "34") (pinfunction "34_34") (pintype "passive"))
      (node (ref "R12") (pin "1") (pinfunction "1_1") (pintype "passive"))
    )
    (net (code "6") (name "/C1+") (class "Default")
      (node (ref "C7") (pin "2") (pinfunction "2_2") (pintype "passive"))
      (node (ref "D3") (pin "1") (pinfunction "K_1") (pintype "bidirectional"))
      (node (ref "JP7") (pin "16_C1+") (pinfunction "16_C1+_16_C1+") (pintype "passive"))
      (node (ref "Q2") (pin "2") (pinfunction "S_2") (pintype "bidirectional"))
      (node (ref "R12") (pin "2") (pinfunction "2_2") (pintype "passive"))
      (node (ref "R14") (pin "1") (pinfunction "1_1") (pintype "passive"))
      (node (ref "R23") (pin "2") (pinfunction "2_2") (pintype "passive"))
    )
    (net (code "7") (name "/C1-") (class "Default")
      (node (ref "C5") (pin "2") (pinfunction "2_2") (pintype "passive"))
      (node (ref "C6") (pin "2") (pinfunction "2_2") (pintype "passive"))
      (node (ref "D3") (pin "2") (pinfunction "A_2") (pintype "bidirectional"))
      (node (ref "JP7") (pin "15_TOTAL-") (pinfunction "15_TOTAL-_15_TOTAL-") (pintype "passive"))
      (node (ref "R11") (pin "2") (pinfunction "2_2") (pintype "passive"))
      (node (ref "R3") (pin "2") (pinfunction "2_2") (pintype "passive"))
      (node (ref "R4") (pin "1") (pinfunction "1_1") (pintype "passive"))
    )
    (net (code "8") (name "/C2") (class "Default")
      (node (ref "C7") (pin "1") (pinfunction "1_1") (pintype "passive"))
      (node (ref "JP5") (pin "38") (pinfunction "38_38") (pintype "passive"))
      (node (ref "R24") (pin "1") (pinfunction "1_1") (pintype "passive"))
    )
    (net (code "9") (name "/C2+") (class "Default")
      (node (ref "C9") (pin "2") (pinfunction "2_2") (pintype "passive"))
      (node (ref "JP7") (pin "13_C2+") (pinfunction "13_C2+_13_C2+") (pintype "passive"))
      (node (ref "Q3") (pin "2") (pinfunction "S_2") (pintype "bidirectional"))
      (node (ref "R24") (pin "2") (pinfunction "2_2") (pintype "passive"))
      (node (ref "R31") (pin "1") (pinfunction "1_1") (pintype "passive"))
      (node (ref "R35") (pin "2") (pinfunction "2_2") (pintype "passive"))
    )
    (net (code "10") (name "/C3") (class "Default")
      (node (ref "C9") (pin "1") (pinfunction "1_1") (pintype "passive"))
      (node (ref "JP5") (pin "39") (pinfunction "39_39") (pintype "passive"))
      (node (ref "R36") (pin "1") (pinfunction "1_1") (pintype "passive"))
    )
    (net (code "11") (name "/C3+") (class "Default")
      (node (ref "C8") (pin "2") (pinfunction "2_2") (pintype "passive"))
      (node (ref "JP7") (pin "14_C3+") (pinfunction "14_C3+_14_C3+") (pintype "passive"))
      (node (ref "Q5") (pin "2") (pinfunction "S_2") (pintype "bidirectional"))
      (node (ref "R25") (pin "1") (pinfunction "1_1") (pintype "passive"))
      (node (ref "R29") (pin "2") (pinfunction "2_2") (pintype "passive"))
      (node (ref "R36") (pin "2") (pinfunction "2_2") (pintype "passive"))
    )
    (net (code "12") (name "/C4") (class "Default")
      (node (ref "C8") (pin "1") (pinfunction "1_1") (pintype "passive"))
      (node (ref "JP5") (pin "35") (pinfunction "35_35") (pintype "passive"))
      (node (ref "R30") (pin "1") (pinfunction "1_1") (pintype "passive"))
    )
    (net (code "13") (name "/C4+") (class "Default")
      (node (ref "C12") (pin "2") (pinfunction "2_2") (pintype "passive"))
      (node (ref "JP7") (pin "10_C5+") (pinfunction "10_C5+_10_C5+") (pintype "passive"))
      (node (ref "JP7") (pin "11_C4+") (pinfunction "11_C4+_11_C4+") (pintype "passive"))
      (node (ref "JP7") (pin "5_C8+") (pinfunction "5_C8+_5_C8+") (pintype "passive"))
      (node (ref "JP7") (pin "7_C6+") (pinfunction "7_C6+_7_C6+") (pintype "passive"))
      (node (ref "JP7") (pin "8_C7+") (pinfunction "8_C7+_8_C7+") (pintype "passive"))
      (node (ref "Q4") (pin "2") (pinfunction "S_2") (pintype "bidirectional"))
      (node (ref "R18") (pin "2") (pinfunction "2_2") (pintype "passive"))
      (node (ref "R30") (pin "2") (pinfunction "2_2") (pintype "passive"))
      (node (ref "R49") (pin "1") (pinfunction "1_1") (pintype "passive"))
      (node (ref "R63") (pin "2") (pinfunction "2_2") (pintype "passive"))
    )
    (net (code "14") (name "/C5") (class "Default")
      (node (ref "JP5") (pin "31") (pinfunction "31_31") (pintype "passive"))
      (node (ref "R17") (pin "1") (pinfunction "1_1") (pintype "passive"))
    )
    (net (code "15") (name "/C5+") (class "Default")
      (node (ref "C13") (pin "2") (pinfunction "2_2") (pintype "passive"))
      (node (ref "JP7") (pin "6_C9+") (pinfunction "6_C9+_6_C9+") (pintype "passive"))
      (node (ref "Q8") (pin "2") (pinfunction "S_2") (pintype "bidirectional"))
      (node (ref "R64") (pin "2") (pinfunction "2_2") (pintype "passive"))
      (node (ref "R65") (pin "1") (pinfunction "1_1") (pintype "passive"))
      (node (ref "R69") (pin "2") (pinfunction "2_2") (pintype "passive"))
    )
    (net (code "16") (name "/C6") (class "Default")
      (node (ref "JP5") (pin "27") (pinfunction "27_27") (pintype "passive"))
      (node (ref "R17") (pin "2") (pinfunction "2_2") (pintype "passive"))
      (node (ref "R18") (pin "1") (pinfunction "1_1") (pintype "passive"))
    )
    (net (code "17") (name "/C6+") (class "Default")
      (node (ref "C14") (pin "2") (pinfunction "2_2") (pintype "passive"))
      (node (ref "JP7") (pin "3_C10+") (pinfunction "3_C10+_3_C10+") (pintype "passive"))
      (node (ref "Q9") (pin "2") (pinfunction "S_2") (pintype "bidirectional"))
      (node (ref "R70") (pin "2") (pinfunction "2_2") (pintype "passive"))
      (node (ref "R71") (pin "1") (pinfunction "1_1") (pintype "passive"))
      (node (ref "R75") (pin "2") (pinfunction "2_2") (pintype "passive"))
    )
    (net (code "18") (name "/C7") (class "Default")
      (node (ref "C12") (pin "1") (pinfunction "1_1") (pintype "passive"))
      (node (ref "JP5") (pin "23") (pinfunction "23_23") (pintype "passive"))
      (node (ref "R64") (pin "1") (pinfunction "1_1") (pintype "passive"))
    )
    (net (code "19") (name "/C7+") (class "Default")
      (node (ref "C15") (pin "2") (pinfunction "2_2") (pintype "passive"))
      (node (ref "JP7") (pin "4_C11+") (pinfunction "4_C11+_4_C11+") (pintype "passive"))
      (node (ref "Q10") (pin "2") (pinfunction "S_2") (pintype "bidirectional"))
      (node (ref "R76") (pin "2") (pinfunction "2_2") (pintype "passive"))
      (node (ref "R77") (pin "1") (pinfunction "1_1") (pintype "passive"))
      (node (ref "R81") (pin "2") (pinfunction "2_2") (pintype "passive"))
    )
    (net (code "20") (name "/C8") (class "Default")
      (node (ref "C13") (pin "1") (pinfunction "1_1") (pintype "passive"))
      (node (ref "JP5") (pin "19") (pinfunction "19_19") (pintype "passive"))
      (node (ref "R70") (pin "1") (pinfunction "1_1") (pintype "passive"))
    )
    (net (code "21") (name "/C8+") (class "Default")
      (node (ref "JP7") (pin "2_TOTAL+2") (pinfunction "2_CTOTAL+_2_TOTAL+2") (pintype "passive"))
      (node (ref "Q11") (pin "2") (pinfunction "S_2") (pintype "bidirectional"))
      (node (ref "R38") (pin "2") (pinfunction "2_2") (pintype "passive"))
      (node (ref "R83") (pin "2") (pinfunction "2_2") (pintype "passive"))
    )
    (net (code "22") (name "/C9") (class "Default")
      (node (ref "C14") (pin "1") (pinfunction "1_1") (pintype "passive"))
      (node (ref "JP5") (pin "15") (pinfunction "15_15") (pintype "passive"))
      (node (ref "R76") (pin "1") (pinfunction "1_1") (pintype "passive"))
    )
    (net (code "23") (name "/C10") (class "Default")
      (node (ref "C15") (pin "1") (pinfunction "1_1") (pintype "passive"))
      (node (ref "JP5") (pin "11") (pinfunction "11_11") (pintype "passive"))
      (node (ref "R83") (pin "1") (pinfunction "1_1") (pintype "passive"))
    )
    (net (code "24") (name "/C11") (class "Default")
      (node (ref "JP5") (pin "7") (pinfunction "7_7") (pintype "passive"))
      (node (ref "R37") (pin "1") (pinfunction "1_1") (pintype "passive"))
    )
    (net (code "25") (name "/C12") (class "Default")
      (node (ref "JP5") (pin "3") (pinfunction "3_3") (pintype "passive"))
      (node (ref "R37") (pin "2") (pinfunction "2_2") (pintype "passive"))
      (node (ref "R38") (pin "1") (pinfunction "1_1") (pintype "passive"))
    )
    (net (code "26") (name "/CSB") (class "Default")
      (node (ref "JP5") (pin "8") (pinfunction "8_8") (pintype "passive"))
      (node (ref "R6") (pin "2") (pinfunction "2_2") (pintype "passive"))
    )
    (net (code "27") (name "/GND") (class "Default")
      (node (ref "C1") (pin "-") (pinfunction "-_-") (pintype "passive"))
      (node (ref "C18") (pin "2") (pinfunction "2_2") (pintype "passive"))
      (node (ref "C19") (pin "2") (pinfunction "2_2") (pintype "passive"))
      (node (ref "C2") (pin "-") (pinfunction "-_-") (pintype "passive"))
      (node (ref "C20") (pin "1") (pinfunction "1_1") (pintype "passive"))
      (node (ref "C3") (pin "-") (pinfunction "-_-") (pintype "passive"))
      (node (ref "C4") (pin "2") (pinfunction "2_2") (pintype "passive"))
      (node (ref "JP10") (pin "1") (pinfunction "1_1") (pintype "passive"))
      (node (ref "JP10") (pin "2") (pinfunction "2_2") (pintype "passive"))
      (node (ref "JP11") (pin "1") (pinfunction "1_1") (pintype "passive"))
      (node (ref "JP11") (pin "2") (pinfunction "2_2") (pintype "passive"))
      (node (ref "JP5") (pin "16") (pinfunction "16_16") (pintype "passive"))
      (node (ref "JP5") (pin "18") (pinfunction "18_18") (pintype "passive"))
      (node (ref "JP7") (pin "17_TOTAL-") (pinfunction "TOTAL-_17_TOTAL-") (pintype "passive"))
      (node (ref "JP9") (pin "4") (pinfunction "4_4") (pintype "passive"))
      (node (ref "JP9") (pin "5") (pinfunction "5_5") (pintype "passive"))
      (node (ref "LED1") (pin "C") (pinfunction "C_C") (pintype "passive"))
      (node (ref "LED2") (pin "C") (pinfunction "C_C") (pintype "passive"))
      (node (ref "LED3") (pin "C") (pinfunction "C_C") (pintype "passive"))
      (node (ref "LED4") (pin "C") (pinfunction "C_C") (pintype "passive"))
      (node (ref "R16") (pin "1") (pinfunction "1_1") (pintype "passive"))
      (node (ref "R57") (pin "1") (pinfunction "1_1") (pintype "passive"))
      (node (ref "R58") (pin "1") (pinfunction "1_1") (pintype "passive"))
      (node (ref "U$1") (pin "IN-") (pinfunction "IN-_IN-") (pintype "bidirectional"))
      (node (ref "U$1") (pin "OUT-") (pinfunction "OUT-_OUT-") (pintype "bidirectional"))
      (node (ref "U$2") (pin "JP2.7") (pinfunction "GND_JP2.7") (pintype "power_in"))
    )
    (net (code "28") (name "/GPIO4") (class "Default")
      (node (ref "JP5") (pin "22") (pinfunction "22_22") (pintype "passive"))
    )
    (net (code "29") (name "/GPIO5") (class "Default")
      (node (ref "JP5") (pin "20") (pinfunction "20_20") (pintype "passive"))
    )
    (net (code "30") (name "/ISIGNAL") (class "Default")
      (node (ref "JP5") (pin "24") (pinfunction "24_24") (pintype "passive"))
      (node (ref "JP9") (pin "3") (pinfunction "3_3") (pintype "passive"))
    )
    (net (code "31") (name "/MISO") (class "Default")
      (node (ref "JP5") (pin "2") (pinfunction "2_2") (pintype "passive"))
      (node (ref "R2") (pin "1") (pinfunction "1_1") (pintype "passive"))
      (node (ref "R61") (pin "2") (pinfunction "2_2") (pintype "passive"))
    )
    (net (code "32") (name "/MOSI") (class "Default")
      (node (ref "JP5") (pin "4") (pinfunction "4_4") (pintype "passive"))
      (node (ref "R1") (pin "1") (pinfunction "1_1") (pintype "passive"))
      (node (ref "R62") (pin "2") (pinfunction "2_2") (pintype "passive"))
    )
    (net (code "33") (name "/S1") (class "Default")
      (node (ref "JP5") (pin "32") (pinfunction "32_32") (pintype "passive"))
      (node (ref "R10") (pin "1") (pinfunction "1_1") (pintype "passive"))
    )
    (net (code "34") (name "/S2") (class "Default")
      (node (ref "JP5") (pin "36") (pinfunction "36_36") (pintype "passive"))
      (node (ref "R22") (pin "1") (pinfunction "1_1") (pintype "passive"))
    )
    (net (code "35") (name "/S3") (class "Default")
      (node (ref "JP5") (pin "40") (pinfunction "40_40") (pintype "passive"))
      (node (ref "R34") (pin "1") (pinfunction "1_1") (pintype "passive"))
    )
    (net (code "36") (name "/S4") (class "Default")
      (node (ref "JP5") (pin "37") (pinfunction "37_37") (pintype "passive"))
      (node (ref "R28") (pin "1") (pinfunction "1_1") (pintype "passive"))
    )
    (net (code "37") (name "/S5") (class "Default")
      (node (ref "JP5") (pin "33") (pinfunction "33_33") (pintype "passive"))
    )
    (net (code "38") (name "/S6") (class "Default")
      (node (ref "JP5") (pin "29") (pinfunction "29_29") (pintype "passive"))
    )
    (net (code "39") (name "/S7") (class "Default")
      (node (ref "JP5") (pin "25") (pinfunction "25_25") (pintype "passive"))
      (node (ref "R52") (pin "1") (pinfunction "1_1") (pintype "passive"))
    )
    (net (code "40") (name "/S8") (class "Default")
      (node (ref "JP5") (pin "21") (pinfunction "21_21") (pintype "passive"))
      (node (ref "R68") (pin "1") (pinfunction "1_1") (pintype "passive"))
    )
    (net (code "41") (name "/S9") (class "Default")
      (node (ref "JP5") (pin "17") (pinfunction "17_17") (pintype "passive"))
      (node (ref "R74") (pin "1") (pinfunction "1_1") (pintype "passive"))
    )
    (net (code "42") (name "/S10") (class "Default")
      (node (ref "JP5") (pin "13") (pinfunction "13_13") (pintype "passive"))
      (node (ref "R80") (pin "1") (pinfunction "1_1") (pintype "passive"))
    )
    (net (code "43") (name "/S11") (class "Default")
      (node (ref "JP5") (pin "9") (pinfunction "9_9") (pintype "passive"))
    )
    (net (code "44") (name "/S12") (class "Default")
      (node (ref "JP5") (pin "5") (pinfunction "5_5") (pintype "passive"))
    )
    (net (code "45") (name "/SCK") (class "Default")
      (node (ref "JP5") (pin "6") (pinfunction "6_6") (pintype "passive"))
      (node (ref "R5") (pin "2") (pinfunction "2_2") (pintype "passive"))
    )
    (net (code "46") (name "/V+") (class "Default")
      (node (ref "C20") (pin "2") (pinfunction "2_2") (pintype "passive"))
      (node (ref "JP5") (pin "1") (pinfunction "1_1") (pintype "passive"))
      (node (ref "R9") (pin "1") (pinfunction "1_1") (pintype "passive"))
    )
    (net (code "47") (name "/VIN") (class "Default")
      (node (ref "D2") (pin "1") (pinfunction "K_1") (pintype "bidirectional"))
      (node (ref "JP7") (pin "1_TOTAL+") (pinfunction "1_TOTAL+_1_TOTAL+") (pintype "passive"))
      (node (ref "R15") (pin "2") (pinfunction "2_2") (pintype "passive"))
      (node (ref "R9") (pin "2") (pinfunction "2_2") (pintype "passive"))
      (node (ref "U$1") (pin "IN+") (pinfunction "IN+_IN+") (pintype "bidirectional"))
    )
    (net (code "48") (name "/VREF1") (class "Default")
      (node (ref "C1") (pin "+") (pinfunction "+_+") (pintype "passive"))
      (node (ref "C18") (pin "1") (pinfunction "1_1") (pintype "passive"))
      (node (ref "JP5") (pin "12") (pinfunction "12_12") (pintype "passive"))
    )
    (net (code "49") (name "/VREF2") (class "Default")
      (node (ref "C2") (pin "+") (pinfunction "+_+") (pintype "passive"))
      (node (ref "C4") (pin "1") (pinfunction "1_1") (pintype "passive"))
      (node (ref "JP5") (pin "14") (pinfunction "14_14") (pintype "passive"))
      (node (ref "JP7") (pin "19_THERMO1_IN") (pinfunction "19_THERMO1_IN_19_THERMO1_IN") (pintype "passive"))
      (node (ref "JP7") (pin "20_THERMO2_IN") (pinfunction "20_THERMO2_IN_20_THERMO2_IN") (pintype "passive"))
    )
    (net (code "50") (name "/VTEMP1") (class "Default")
      (node (ref "JP5") (pin "28") (pinfunction "28_28") (pintype "passive"))
      (node (ref "JP7") (pin "21_THERMO1_OUT") (pinfunction "21_THERMO1_OUT_21_THERMO1_OUT") (pintype "passive"))
      (node (ref "R57") (pin "2") (pinfunction "2_2") (pintype "passive"))
    )
    (net (code "51") (name "/VTEMP2") (class "Default")
      (node (ref "JP5") (pin "26") (pinfunction "26_26") (pintype "passive"))
      (node (ref "JP7") (pin "22_THERMO2_OUT") (pinfunction "22_THERMO2_OUT_22_THERMO2_OUT") (pintype "passive"))
      (node (ref "R58") (pin "2") (pinfunction "2_2") (pintype "passive"))
    )
    (net (code "52") (name "Net-(LED1-PadA)") (class "Default")
      (node (ref "LED1") (pin "A") (pinfunction "A_A") (pintype "passive"))
      (node (ref "R53") (pin "1") (pinfunction "1_1") (pintype "passive"))
    )
    (net (code "53") (name "Net-(LED2-PadA)") (class "Default")
      (node (ref "LED2") (pin "A") (pinfunction "A_A") (pintype "passive"))
      (node (ref "R54") (pin "1") (pinfunction "1_1") (pintype "passive"))
    )
    (net (code "54") (name "Net-(LED3-PadA)") (class "Default")
      (node (ref "LED3") (pin "A") (pinfunction "A_A") (pintype "passive"))
      (node (ref "R55") (pin "1") (pinfunction "1_1") (pintype "passive"))
    )
    (net (code "55") (name "Net-(LED4-PadA)") (class "Default")
      (node (ref "LED4") (pin "A") (pinfunction "A_A") (pintype "passive"))
      (node (ref "R56") (pin "1") (pinfunction "1_1") (pintype "passive"))
    )
    (net (code "56") (name "Net-(LED5-PadC)") (class "Default")
      (node (ref "LED5") (pin "C") (pinfunction "C_C") (pintype "passive"))
      (node (ref "R11") (pin "1") (pinfunction "1_1") (pintype "passive"))
    )
    (net (code "57") (name "Net-(LED6-PadC)") (class "Default")
      (node (ref "LED6") (pin "C") (pinfunction "C_C") (pintype "passive"))
      (node (ref "R23") (pin "1") (pinfunction "1_1") (pintype "passive"))
    )
    (net (code "58") (name "Net-(LED7-PadC)") (class "Default")
      (node (ref "LED7") (pin "C") (pinfunction "C_C") (pintype "passive"))
      (node (ref "R29") (pin "1") (pinfunction "1_1") (pintype "passive"))
    )
    (net (code "59") (name "Net-(LED8-PadC)") (class "Default")
      (node (ref "LED8") (pin "C") (pinfunction "C_C") (pintype "passive"))
      (node (ref "R35") (pin "1") (pinfunction "1_1") (pintype "passive"))
    )
    (net (code "60") (name "Net-(LED12-PadC)") (class "Default")
      (node (ref "LED12") (pin "C") (pinfunction "C_C") (pintype "passive"))
      (node (ref "R63") (pin "1") (pinfunction "1_1") (pintype "passive"))
    )
    (net (code "61") (name "Net-(LED13-PadC)") (class "Default")
      (node (ref "LED13") (pin "C") (pinfunction "C_C") (pintype "passive"))
      (node (ref "R69") (pin "1") (pinfunction "1_1") (pintype "passive"))
    )
    (net (code "62") (name "Net-(LED14-PadC)") (class "Default")
      (node (ref "LED14") (pin "C") (pinfunction "C_C") (pintype "passive"))
      (node (ref "R75") (pin "1") (pinfunction "1_1") (pintype "passive"))
    )
    (net (code "63") (name "Net-(LED15-PadC)") (class "Default")
      (node (ref "LED15") (pin "C") (pinfunction "C_C") (pintype "passive"))
      (node (ref "R81") (pin "1") (pinfunction "1_1") (pintype "passive"))
    )
    (net (code "64") (name "Net-(Q2-D)") (class "Default")
      (node (ref "LED5") (pin "A") (pinfunction "A_A") (pintype "passive"))
      (node (ref "Q2") (pin "3") (pinfunction "D_3") (pintype "bidirectional"))
      (node (ref "R8") (pin "2") (pinfunction "2_2") (pintype "passive"))
    )
    (net (code "65") (name "Net-(Q2-G)") (class "Default")
      (node (ref "Q2") (pin "1") (pinfunction "G_1") (pintype "bidirectional"))
      (node (ref "R10") (pin "2") (pinfunction "2_2") (pintype "passive"))
    )
    (net (code "66") (name "Net-(Q3-D)") (class "Default")
      (node (ref "LED6") (pin "A") (pinfunction "A_A") (pintype "passive"))
      (node (ref "Q3") (pin "3") (pinfunction "D_3") (pintype "bidirectional"))
      (node (ref "R21") (pin "2") (pinfunction "2_2") (pintype "passive"))
    )
    (net (code "67") (name "Net-(Q3-G)") (class "Default")
      (node (ref "Q3") (pin "1") (pinfunction "G_1") (pintype "bidirectional"))
      (node (ref "R22") (pin "2") (pinfunction "2_2") (pintype "passive"))
    )
    (net (code "68") (name "Net-(Q4-D)") (class "Default")
      (node (ref "LED7") (pin "A") (pinfunction "A_A") (pintype "passive"))
      (node (ref "Q4") (pin "3") (pinfunction "D_3") (pintype "bidirectional"))
      (node (ref "R27") (pin "2") (pinfunction "2_2") (pintype "passive"))
    )
    (net (code "69") (name "Net-(Q4-G)") (class "Default")
      (node (ref "Q4") (pin "1") (pinfunction "G_1") (pintype "bidirectional"))
      (node (ref "R28") (pin "2") (pinfunction "2_2") (pintype "passive"))
    )
    (net (code "70") (name "Net-(Q5-D)") (class "Default")
      (node (ref "LED8") (pin "A") (pinfunction "A_A") (pintype "passive"))
      (node (ref "Q5") (pin "3") (pinfunction "D_3") (pintype "bidirectional"))
      (node (ref "R33") (pin "2") (pinfunction "2_2") (pintype "passive"))
    )
    (net (code "71") (name "Net-(Q5-G)") (class "Default")
      (node (ref "Q5") (pin "1") (pinfunction "G_1") (pintype "bidirectional"))
      (node (ref "R34") (pin "2") (pinfunction "2_2") (pintype "passive"))
    )
    (net (code "72") (name "Net-(Q8-D)") (class "Default")
      (node (ref "LED12") (pin "A") (pinfunction "A_A") (pintype "passive"))
      (node (ref "Q8") (pin "3") (pinfunction "D_3") (pintype "bidirectional"))
      (node (ref "R51") (pin "2") (pinfunction "2_2") (pintype "passive"))
    )
    (net (code "73") (name "Net-(Q8-G)") (class "Default")
      (node (ref "Q8") (pin "1") (pinfunction "G_1") (pintype "bidirectional"))
      (node (ref "R52") (pin "2") (pinfunction "2_2") (pintype "passive"))
    )
    (net (code "74") (name "Net-(Q9-D)") (class "Default")
      (node (ref "LED13") (pin "A") (pinfunction "A_A") (pintype "passive"))
      (node (ref "Q9") (pin "3") (pinfunction "D_3") (pintype "bidirectional"))
      (node (ref "R67") (pin "2") (pinfunction "2_2") (pintype "passive"))
    )
    (net (code "75") (name "Net-(Q9-G)") (class "Default")
      (node (ref "Q9") (pin "1") (pinfunction "G_1") (pintype "bidirectional"))
      (node (ref "R68") (pin "2") (pinfunction "2_2") (pintype "passive"))
    )
    (net (code "76") (name "Net-(Q10-D)") (class "Default")
      (node (ref "LED14") (pin "A") (pinfunction "A_A") (pintype "passive"))
      (node (ref "Q10") (pin "3") (pinfunction "D_3") (pintype "bidirectional"))
      (node (ref "R73") (pin "2") (pinfunction "2_2") (pintype "passive"))
    )
    (net (code "77") (name "Net-(Q10-G)") (class "Default")
      (node (ref "Q10") (pin "1") (pinfunction "G_1") (pintype "bidirectional"))
      (node (ref "R74") (pin "2") (pinfunction "2_2") (pintype "passive"))
    )
    (net (code "78") (name "Net-(Q11-D)") (class "Default")
      (node (ref "LED15") (pin "A") (pinfunction "A_A") (pintype "passive"))
      (node (ref "Q11") (pin "3") (pinfunction "D_3") (pintype "bidirectional"))
      (node (ref "R79") (pin "2") (pinfunction "2_2") (pintype "passive"))
    )
    (net (code "79") (name "Net-(Q11-G)") (class "Default")
      (node (ref "Q11") (pin "1") (pinfunction "G_1") (pintype "bidirectional"))
      (node (ref "R80") (pin "2") (pinfunction "2_2") (pintype "passive"))
    )
    (net (code "80") (name "Net-(R4-Pad2)") (class "Default")
      (node (ref "R4") (pin "2") (pinfunction "2_2") (pintype "passive"))
      (node (ref "R7") (pin "1") (pinfunction "1_1") (pintype "passive"))
    )
    (net (code "81") (name "Net-(R7-Pad2)") (class "Default")
      (node (ref "R7") (pin "2") (pinfunction "2_2") (pintype "passive"))
      (node (ref "R8") (pin "1") (pinfunction "1_1") (pintype "passive"))
    )
    (net (code "82") (name "Net-(R14-Pad2)") (class "Default")
      (node (ref "R14") (pin "2") (pinfunction "2_2") (pintype "passive"))
      (node (ref "R20") (pin "1") (pinfunction "1_1") (pintype "passive"))
    )
    (net (code "83") (name "Net-(R20-Pad2)") (class "Default")
      (node (ref "R20") (pin "2") (pinfunction "2_2") (pintype "passive"))
      (node (ref "R21") (pin "1") (pinfunction "1_1") (pintype "passive"))
    )
    (net (code "84") (name "Net-(R25-Pad2)") (class "Default")
      (node (ref "R25") (pin "2") (pinfunction "2_2") (pintype "passive"))
      (node (ref "R26") (pin "1") (pinfunction "1_1") (pintype "passive"))
    )
    (net (code "85") (name "Net-(R26-Pad2)") (class "Default")
      (node (ref "R26") (pin "2") (pinfunction "2_2") (pintype "passive"))
      (node (ref "R27") (pin "1") (pinfunction "1_1") (pintype "passive"))
    )
    (net (code "86") (name "Net-(R31-Pad2)") (class "Default")
      (node (ref "R31") (pin "2") (pinfunction "2_2") (pintype "passive"))
      (node (ref "R32") (pin "1") (pinfunction "1_1") (pintype "passive"))
    )
    (net (code "87") (name "Net-(R32-Pad2)") (class "Default")
      (node (ref "R32") (pin "2") (pinfunction "2_2") (pintype "passive"))
      (node (ref "R33") (pin "1") (pinfunction "1_1") (pintype "passive"))
    )
    (net (code "88") (name "Net-(R49-Pad2)") (class "Default")
      (node (ref "R49") (pin "2") (pinfunction "2_2") (pintype "passive"))
      (node (ref "R50") (pin "1") (pinfunction "1_1") (pintype "passive"))
    )
    (net (code "89") (name "Net-(R50-Pad2)") (class "Default")
      (node (ref "R50") (pin "2") (pinfunction "2_2") (pintype "passive"))
      (node (ref "R51") (pin "1") (pinfunction "1_1") (pintype "passive"))
    )
    (net (code "90") (name "Net-(R65-Pad2)") (class "Default")
      (node (ref "R65") (pin "2") (pinfunction "2_2") (pintype "passive"))
      (node (ref "R66") (pin "1") (pinfunction "1_1") (pintype "passive"))
    )
    (net (code "91") (name "Net-(R66-Pad2)") (class "Default")
      (node (ref "R66") (pin "2") (pinfunction "2_2") (pintype "passive"))
      (node (ref "R67") (pin "1") (pinfunction "1_1") (pintype "passive"))
    )
    (net (code "92") (name "Net-(R71-Pad2)") (class "Default")
      (node (ref "R71") (pin "2") (pinfunction "2_2") (pintype "passive"))
      (node (ref "R72") (pin "1") (pinfunction "1_1") (pintype "passive"))
    )
    (net (code "93") (name "Net-(R72-Pad2)") (class "Default")
      (node (ref "R72") (pin "2") (pinfunction "2_2") (pintype "passive"))
      (node (ref "R73") (pin "1") (pinfunction "1_1") (pintype "passive"))
    )
    (net (code "94") (name "Net-(R77-Pad2)") (class "Default")
      (node (ref "R77") (pin "2") (pinfunction "2_2") (pintype "passive"))
      (node (ref "R78") (pin "1") (pinfunction "1_1") (pintype "passive"))
    )
    (net (code "95") (name "Net-(R78-Pad2)") (class "Default")
      (node (ref "R78") (pin "2") (pinfunction "2_2") (pintype "passive"))
      (node (ref "R79") (pin "1") (pinfunction "1_1") (pintype "passive"))
    )
    (net (code "96") (name "Net-(U$2-D0)") (class "Default")
      (node (ref "JP3") (pin "1") (pinfunction "1_1") (pintype "passive"))
      (node (ref "U$2") (pin "JP1.3") (pinfunction "D0_JP1.3") (pintype "bidirectional"))
    )
    (net (code "97") (name "Net-(U$2-D1)") (class "Default")
      (node (ref "R53") (pin "2") (pinfunction "2_2") (pintype "passive"))
      (node (ref "U$2") (pin "JP2.3") (pinfunction "D1_JP2.3") (pintype "bidirectional"))
    )
    (net (code "98") (name "Net-(U$2-D2)") (class "Default")
      (node (ref "R54") (pin "2") (pinfunction "2_2") (pintype "passive"))
      (node (ref "U$2") (pin "JP2.4") (pinfunction "D2_JP2.4") (pintype "bidirectional"))
    )
    (net (code "99") (name "Net-(U$2-D3)") (class "Default")
      (node (ref "R55") (pin "2") (pinfunction "2_2") (pintype "passive"))
      (node (ref "U$2") (pin "JP2.5") (pinfunction "D3_JP2.5") (pintype "bidirectional"))
    )
    (net (code "100") (name "Net-(U$2-D4)") (class "Default")
      (node (ref "R56") (pin "2") (pinfunction "2_2") (pintype "passive"))
      (node (ref "U$2") (pin "JP2.6") (pinfunction "D4_JP2.6") (pintype "bidirectional"))
    )
    (net (code "101") (name "Net-(U$2-D5)") (class "Default")
      (node (ref "R5") (pin "1") (pinfunction "1_1") (pintype "passive"))
      (node (ref "U$2") (pin "JP1.4") (pinfunction "D5_JP1.4") (pintype "bidirectional"))
    )
    (net (code "102") (name "Net-(U$2-D6)") (class "Default")
      (node (ref "R61") (pin "1") (pinfunction "1_1") (pintype "passive"))
      (node (ref "U$2") (pin "JP1.5") (pinfunction "D6_JP1.5") (pintype "bidirectional"))
    )
    (net (code "103") (name "Net-(U$2-D7)") (class "Default")
      (node (ref "R62") (pin "1") (pinfunction "1_1") (pintype "passive"))
      (node (ref "U$2") (pin "JP1.6") (pinfunction "D7_JP1.6") (pintype "bidirectional"))
    )
    (net (code "104") (name "Net-(U$2-D8)") (class "Default")
      (node (ref "R6") (pin "1") (pinfunction "1_1") (pintype "passive"))
      (node (ref "U$2") (pin "JP1.7") (pinfunction "D8_JP1.7") (pintype "bidirectional"))
    )
    (net (code "105") (name "Net-(U$2-RST)") (class "Default")
      (node (ref "JP3") (pin "2") (pinfunction "2_2") (pintype "passive"))
      (node (ref "U$2") (pin "JP1.1") (pinfunction "RST_JP1.1") (pintype "bidirectional"))
    )
    (net (code "106") (name "unconnected-(JP7-Pad9)") (class "Default")
      (node (ref "JP7") (pin "9") (pinfunction "9_9") (pintype "passive"))
    )
    (net (code "107") (name "unconnected-(JP7-Pad12)") (class "Default")
      (node (ref "JP7") (pin "12") (pinfunction "12_12") (pintype "passive"))
    )
    (net (code "108") (name "unconnected-(JP7-Pad18)") (class "Default")
      (node (ref "JP7") (pin "18") (pinfunction "18_18") (pintype "passive"))
    )
    (net (code "109") (name "unconnected-(U$2-RX-PadJP2.2)") (class "Default")
      (node (ref "U$2") (pin "JP2.2") (pinfunction "RX_JP2.2") (pintype "bidirectional"))
    )
    (net (code "110") (name "unconnected-(U$2-TX-PadJP2.1)") (class "Default")
      (node (ref "U$2") (pin "JP2.1") (pinfunction "TX_JP2.1") (pintype "bidirectional"))
    )
  )
)
